# som_fpga.net
KiCad netlist of a schematic drawn in Altium Designer
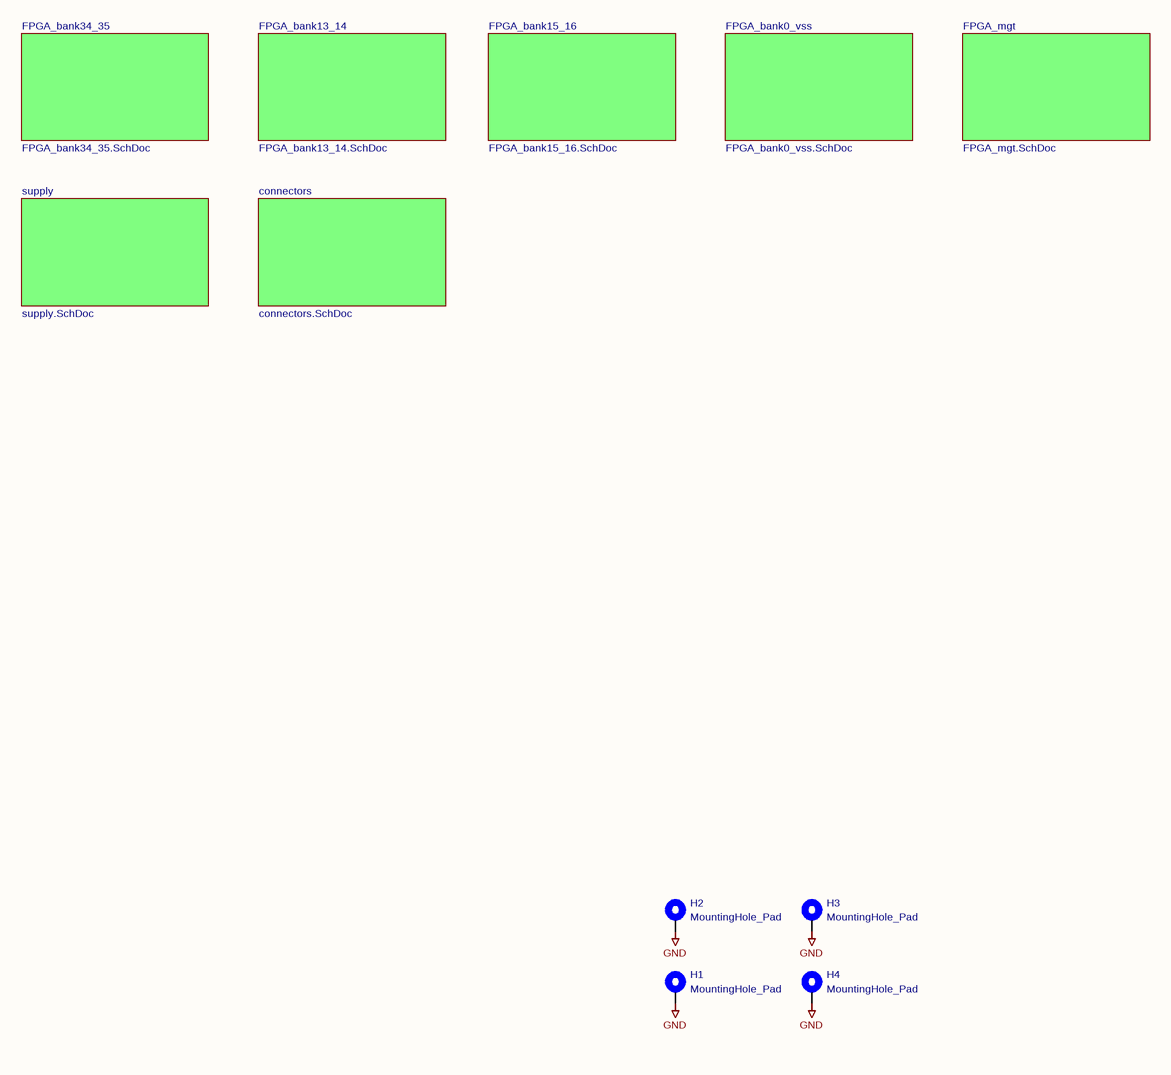
[diagram p0: som_fpga.SchDoc]

(export (version "E")
  (design (tool "Eeschema 10.0.6"))
  (components
    (comp (ref "H1")
      (value "MountingHole_Pad")
      (footprint "MountingHole_3.2mm_M3_ISO7380_Pad")
      (libsource (lib "Mechanical") (part "MountingHole_Pad"))
    )
    (comp (ref "H2")
      (value "MountingHole_Pad")
      (footprint "MountingHole_3.2mm_M3_ISO7380_Pad")
      (libsource (lib "Mechanical") (part "MountingHole_Pad"))
    )
    (comp (ref "H3")
      (value "MountingHole_Pad")
      (footprint "MountingHole_3.2mm_M3_ISO7380_Pad")
      (libsource (lib "Mechanical") (part "MountingHole_Pad"))
    )
    (comp (ref "H4")
      (value "MountingHole_Pad")
      (footprint "MountingHole_3.2mm_M3_ISO7380_Pad")
      (libsource (lib "Mechanical") (part "MountingHole_Pad"))
    )
  )
  (nets
    (net (code "1") (name "GND") (class "Default")
      (node (ref "H1") (pin "1") (pinfunction "1_1") (pintype "passive"))
      (node (ref "H2") (pin "1") (pinfunction "1_1") (pintype "passive"))
      (node (ref "H3") (pin "1") (pinfunction "1_1") (pintype "passive"))
      (node (ref "H4") (pin "1") (pinfunction "1_1") (pintype "passive"))
    )
  )
)
